# LM2595sx-3_3.net
KiCad netlist of a schematic drawn in Altium Designer
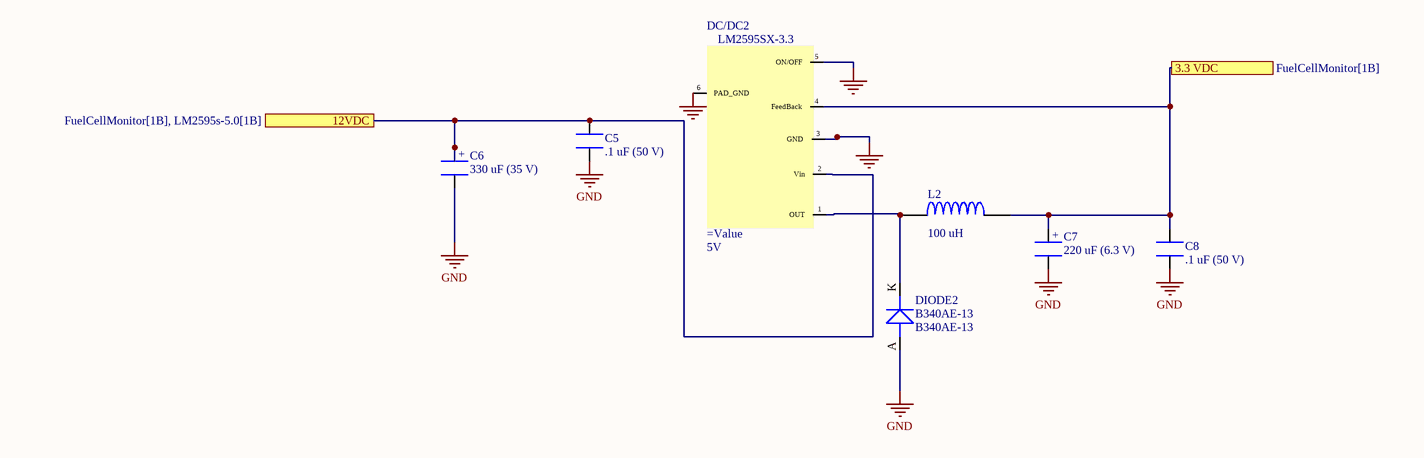
[diagram p0: LM2595sx-3.3.SchDoc]

(export (version "E")
  (design (tool "Eeschema 10.0.6"))
  (components
    (comp (ref "C5")
      (value ".1 uF (50 V)")
      (footprint ".1uF capacitor")
      (libsource (lib "FuelCellMonitor") (part ".1 uF cap"))
    )
    (comp (ref "C6")
      (value "330 uF (35 V)")
      (footprint "330uf cap")
      (libsource (lib "FuelCellMonitor") (part "330 uF cap"))
    )
    (comp (ref "C7")
      (value "220 uF (6.3 V)")
      (footprint "220 uf cap")
      (libsource (lib "FuelCellMonitor") (part "220 uF capacitor"))
    )
    (comp (ref "C8")
      (value ".1 uF (50 V)")
      (footprint ".1uF capacitor")
      (libsource (lib "FuelCellMonitor") (part ".1 uF cap"))
    )
    (comp (ref "DC/DC2")
      (value "~")
      (footprint "LM2595s-3.3")
      (description "SIMPLE SWITCHE Power Converter 150 KHz 1A Step-Down Voltage egulator 5-DDPAK/TO-263")
      (fields
        (field (name "MANUFACTURER") "Texas Instruments")
        (field (name "MANUFACTURER PART NUMBER") "LM2595S-5.0/NOPB")
        (field (name "OUTPUT VOLTAGE") "5V")
      )
      (libsource (lib "FuelCellMonitor") (part "LM2595SX-3.3/NOPB_1"))
    )
    (comp (ref "DIODE2")
      (value "B340AE-13")
      (footprint "B340AE-13")
      (description "Schottky Diode, DO-201, 40V, 3.00A")
      (fields
        (field (name "MANUFACTURER") "STMicroelectronics")
        (field (name "MANUFACTURER PART NUMBER") "B340AE-13")
      )
      (libsource (lib "FuelCellMonitor") (part "B340AE-13"))
    )
    (comp (ref "L2")
      (value "100 uH")
      (footprint "100uH inductor")
      (libsource (lib "FuelCellMonitor") (part "100 uH inductor"))
    )
  )
  (nets
    (net (code "1") (name "/3.3 VDC") (class "Default")
      (node (ref "C7") (pin "1") (pinfunction "1_1") (pintype "power_in"))
      (node (ref "C8") (pin "2") (pinfunction "2_2") (pintype "power_in"))
      (node (ref "DC/DC2") (pin "4") (pinfunction "FeedBack_4") (pintype "power_in"))
      (node (ref "L2") (pin "2") (pinfunction "2_2") (pintype "passive"))
    )
    (net (code "2") (name "/12VDC") (class "Default")
      (node (ref "C5") (pin "2") (pinfunction "2_2") (pintype "power_in"))
      (node (ref "C6") (pin "1") (pinfunction "1_1") (pintype "power_in"))
      (node (ref "DC/DC2") (pin "2") (pinfunction "Vin_2") (pintype "power_in"))
    )
    (net (code "3") (name "GND") (class "Default")
      (node (ref "C5") (pin "1") (pinfunction "1_1") (pintype "power_in"))
      (node (ref "C6") (pin "2") (pinfunction "2_2") (pintype "power_in"))
      (node (ref "C7") (pin "2") (pinfunction "2_2") (pintype "power_in"))
      (node (ref "C8") (pin "1") (pinfunction "1_1") (pintype "power_in"))
      (node (ref "DC/DC2") (pin "3") (pinfunction "GND_3") (pintype "power_in"))
      (node (ref "DC/DC2") (pin "5") (pinfunction "ON/OFF_5") (pintype "power_in"))
      (node (ref "DC/DC2") (pin "6") (pinfunction "PAD_GND_6") (pintype "power_in"))
      (node (ref "DIODE2") (pin "A") (pinfunction "A_A") (pintype "power_in"))
    )
    (net (code "4") (name "Net-(DC/DC2-OUT)") (class "Default")
      (node (ref "DC/DC2") (pin "1") (pinfunction "OUT_1") (pintype "power_in"))
      (node (ref "DIODE2") (pin "K") (pinfunction "K_K") (pintype "power_in"))
      (node (ref "L2") (pin "1") (pinfunction "1_1") (pintype "passive"))
    )
  )
)
